# ESQUEMATICO_BOMBA_MESO.net
KiCad netlist of a schematic drawn in Altium Designer
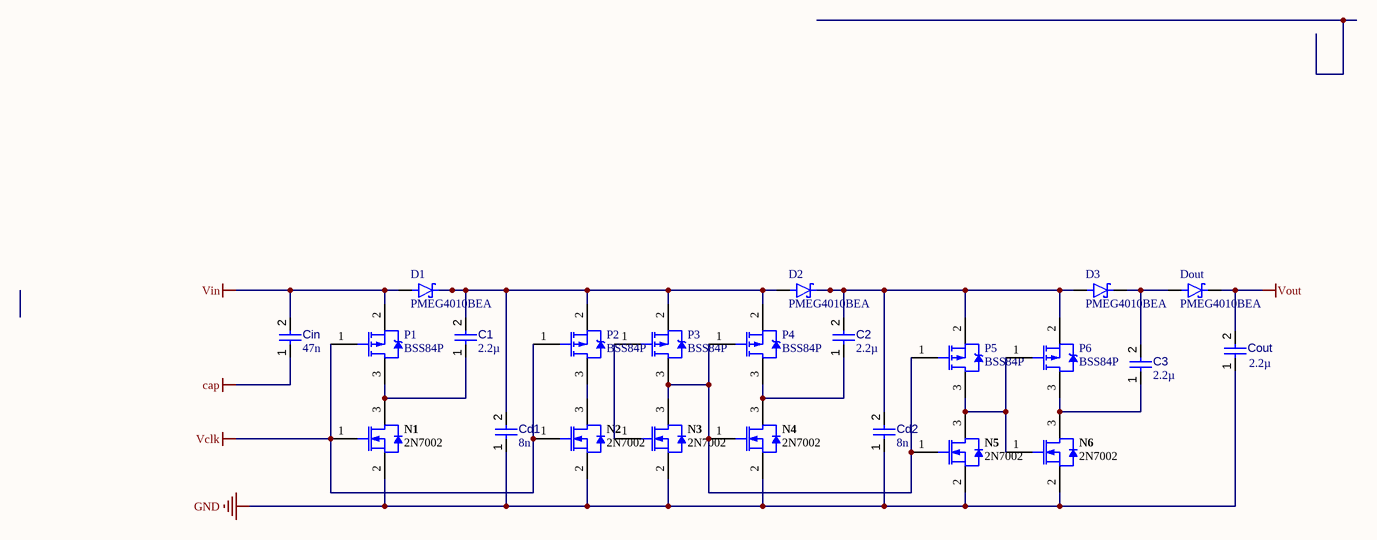
[diagram p0: ESQUEMATICO BOMBA MESO.SchDoc]

(export (version "E")
  (design (tool "Eeschema 10.0.6"))
  (components
    (comp (ref "C1")
      (value "2.2µ")
      (footprint "CAPC2013X135X45NL10T25")
      (description "Chip Capacitor, 10 uF, +/- 10%, 16 V, 0805 (2012 Metric)")
      (fields (field (name "TOLERANCE") "10%") (field (name "Comment") "Capacitor 10 uF +/- 10% 16 V 0805"))
      (libsource (lib "Pontificia Universidad Javeriana") (part "CAP-NP-2"))
    )
    (comp (ref "C2")
      (value "2.2µ")
      (footprint "CAPC2013X135X45NL10T25")
      (description "Chip Capacitor, 10 uF, +/- 10%, 16 V, 0805 (2012 Metric)")
      (fields (field (name "TOLERANCE") "10%") (field (name "Comment") "Capacitor 10 uF +/- 10% 16 V 0805"))
      (libsource (lib "Pontificia Universidad Javeriana") (part "CAP-NP-2"))
    )
    (comp (ref "C3")
      (value "2.2µ")
      (footprint "CAPC2013X135X45NL10T25")
      (description "Chip Capacitor, 10 uF, +/- 10%, 16 V, 0805 (2012 Metric)")
      (fields (field (name "TOLERANCE") "10%") (field (name "Comment") "Capacitor 10 uF +/- 10% 16 V 0805"))
      (libsource (lib "Pontificia Universidad Javeriana") (part "CAP-NP-2"))
    )
    (comp (ref "Cd1")
      (value "8n")
      (footprint "CAPC2013X135X45NL10T25")
      (description "Chip Capacitor, 10 uF, +/- 10%, 16 V, 0805 (2012 Metric)")
      (fields (field (name "TOLERANCE") "10%") (field (name "Comment") "Capacitor 10 uF +/- 10% 16 V 0805"))
      (libsource (lib "Pontificia Universidad Javeriana") (part "CAP-NP-2"))
    )
    (comp (ref "Cd2")
      (value "8n")
      (footprint "CAPC2013X135X45NL10T25")
      (description "Chip Capacitor, 10 uF, +/- 10%, 16 V, 0805 (2012 Metric)")
      (fields (field (name "TOLERANCE") "10%") (field (name "Comment") "Capacitor 10 uF +/- 10% 16 V 0805"))
      (libsource (lib "Pontificia Universidad Javeriana") (part "CAP-NP-2"))
    )
    (comp (ref "Cin")
      (value "47n")
      (footprint "CAPC2013X135X45NL10T25")
      (description "Chip Capacitor, 10 uF, +/- 10%, 16 V, 0805 (2012 Metric)")
      (fields (field (name "TOLERANCE") "10%") (field (name "Comment") "Capacitor 10 uF +/- 10% 16 V 0805"))
      (libsource (lib "Pontificia Universidad Javeriana") (part "CAP-NP-2"))
    )
    (comp (ref "Cout")
      (value "2.2µ")
      (footprint "CAPC2013X135X45NL10T25")
      (description "Chip Capacitor, 10 uF, +/- 10%, 16 V, 0805 (2012 Metric)")
      (fields (field (name "TOLERANCE") "10%") (field (name "Comment") "Capacitor 10 uF +/- 10% 16 V 0805"))
      (libsource (lib "Pontificia Universidad Javeriana") (part "CAP-NP-2"))
    )
    (comp (ref "D1")
      (value "PMEG4010BEA")
      (footprint "DIO_BZX384-C30,115")
      (description "5A, 40V, Schottky Rectifier")
      (fields (field (name "MP") "SS54FSH") (field (name "MF") "Taiwan Semiconductor"))
      (libsource (lib "SS54FSH") (part "SS54FSH"))
    )
    (comp (ref "D2")
      (value "PMEG4010BEA")
      (footprint "DIO_BZX384-C30,115")
      (description "5A, 40V, Schottky Rectifier")
      (fields (field (name "MP") "SS54FSH") (field (name "MF") "Taiwan Semiconductor"))
      (libsource (lib "SS54FSH") (part "SS54FSH"))
    )
    (comp (ref "D3")
      (value "PMEG4010BEA")
      (footprint "DIO_BZX384-C30,115")
      (description "5A, 40V, Schottky Rectifier")
      (fields (field (name "MP") "SS54FSH") (field (name "MF") "Taiwan Semiconductor"))
      (libsource (lib "SS54FSH") (part "SS54FSH"))
    )
    (comp (ref "Dout")
      (value "PMEG4010BEA")
      (footprint "DIO_BZX384-C30,115")
      (description "5A, 40V, Schottky Rectifier")
      (fields (field (name "MP") "SS54FSH") (field (name "MF") "Taiwan Semiconductor"))
      (libsource (lib "SS54FSH") (part "SS54FSH"))
    )
    (comp (ref "N1")
      (value "2N7002")
      (footprint "INF-PG-SOT23_M")
      (fields (field (name "MANUFACTURER") "Infineon"))
      (libsource (lib "Altium Content Vault") (part "INF-NDMOS-GSD-3"))
    )
    (comp (ref "N2")
      (value "2N7002")
      (footprint "INF-PG-SOT23_M")
      (fields (field (name "MANUFACTURER") "Infineon"))
      (libsource (lib "Altium Content Vault") (part "INF-NDMOS-GSD-3"))
    )
    (comp (ref "N3")
      (value "2N7002")
      (footprint "INF-PG-SOT23_M")
      (fields (field (name "MANUFACTURER") "Infineon"))
      (libsource (lib "Altium Content Vault") (part "INF-NDMOS-GSD-3"))
    )
    (comp (ref "N4")
      (value "2N7002")
      (footprint "INF-PG-SOT23_M")
      (fields (field (name "MANUFACTURER") "Infineon"))
      (libsource (lib "Altium Content Vault") (part "INF-NDMOS-GSD-3"))
    )
    (comp (ref "N5")
      (value "2N7002")
      (footprint "INF-PG-SOT23_M")
      (fields (field (name "MANUFACTURER") "Infineon"))
      (libsource (lib "Altium Content Vault") (part "INF-NDMOS-GSD-3"))
    )
    (comp (ref "N6")
      (value "2N7002")
      (footprint "INF-PG-SOT23_M")
      (fields (field (name "MANUFACTURER") "Infineon"))
      (libsource (lib "Altium Content Vault") (part "INF-NDMOS-GSD-3"))
    )
    (comp (ref "P1")
      (value "BSS84P")
      (footprint "INF-PG-SOT23_N")
      (fields (field (name "MANUFACTURER") "Infineon"))
      (libsource (lib "Altium Content Vault") (part "INF-PEMOS-GSD-3-B"))
    )
    (comp (ref "P2")
      (value "BSS84P")
      (footprint "INF-PG-SOT23_N")
      (fields (field (name "MANUFACTURER") "Infineon"))
      (libsource (lib "Altium Content Vault") (part "INF-PEMOS-GSD-3-B"))
    )
    (comp (ref "P3")
      (value "BSS84P")
      (footprint "INF-PG-SOT23_N")
      (fields (field (name "MANUFACTURER") "Infineon"))
      (libsource (lib "Altium Content Vault") (part "INF-PEMOS-GSD-3-B"))
    )
    (comp (ref "P4")
      (value "BSS84P")
      (footprint "INF-PG-SOT23_N")
      (fields (field (name "MANUFACTURER") "Infineon"))
      (libsource (lib "Altium Content Vault") (part "INF-PEMOS-GSD-3-B"))
    )
    (comp (ref "P5")
      (value "BSS84P")
      (footprint "INF-PG-SOT23_N")
      (fields (field (name "MANUFACTURER") "Infineon"))
      (libsource (lib "Altium Content Vault") (part "INF-PEMOS-GSD-3-B"))
    )
    (comp (ref "P6")
      (value "BSS84P")
      (footprint "INF-PG-SOT23_N")
      (fields (field (name "MANUFACTURER") "Infineon"))
      (libsource (lib "Altium Content Vault") (part "INF-PEMOS-GSD-3-B"))
    )
  )
  (nets
    (net (code "1") (name "GND") (class "Default")
      (node (ref "Cd1") (pin "1") (pinfunction "1_1") (pintype "passive"))
      (node (ref "Cd2") (pin "1") (pinfunction "1_1") (pintype "passive"))
      (node (ref "Cout") (pin "1") (pinfunction "1_1") (pintype "passive"))
      (node (ref "N1") (pin "2") (pinfunction "SOURCE_2") (pintype "passive"))
      (node (ref "N2") (pin "2") (pinfunction "SOURCE_2") (pintype "passive"))
      (node (ref "N3") (pin "2") (pinfunction "SOURCE_2") (pintype "passive"))
      (node (ref "N4") (pin "2") (pinfunction "SOURCE_2") (pintype "passive"))
      (node (ref "N5") (pin "2") (pinfunction "SOURCE_2") (pintype "passive"))
      (node (ref "N6") (pin "2") (pinfunction "SOURCE_2") (pintype "passive"))
    )
    (net (code "2") (name "Net-(D1-K)") (class "Default")
      (node (ref "C1") (pin "2") (pinfunction "2_2") (pintype "passive"))
      (node (ref "Cd1") (pin "2") (pinfunction "2_2") (pintype "passive"))
      (node (ref "D1") (pin "C") (pinfunction "K_C") (pintype "passive"))
      (node (ref "D2") (pin "A") (pinfunction "A_A") (pintype "passive"))
      (node (ref "P2") (pin "2") (pinfunction "SOURCE_2") (pintype "passive"))
      (node (ref "P3") (pin "2") (pinfunction "SOURCE_2") (pintype "passive"))
      (node (ref "P4") (pin "2") (pinfunction "SOURCE_2") (pintype "passive"))
    )
    (net (code "3") (name "Net-(D2-K)") (class "Default")
      (node (ref "C2") (pin "2") (pinfunction "2_2") (pintype "passive"))
      (node (ref "Cd2") (pin "2") (pinfunction "2_2") (pintype "passive"))
      (node (ref "D2") (pin "C") (pinfunction "K_C") (pintype "passive"))
      (node (ref "D3") (pin "A") (pinfunction "A_A") (pintype "passive"))
      (node (ref "P5") (pin "2") (pinfunction "SOURCE_2") (pintype "passive"))
      (node (ref "P6") (pin "2") (pinfunction "SOURCE_2") (pintype "passive"))
    )
    (net (code "4") (name "Net-(D3-K)") (class "Default")
      (node (ref "C3") (pin "2") (pinfunction "2_2") (pintype "passive"))
      (node (ref "D3") (pin "C") (pinfunction "K_C") (pintype "passive"))
      (node (ref "Dout") (pin "A") (pinfunction "A_A") (pintype "passive"))
    )
    (net (code "5") (name "Net-(N1-DRAIN)") (class "Default")
      (node (ref "C1") (pin "1") (pinfunction "1_1") (pintype "passive"))
      (node (ref "N1") (pin "3") (pinfunction "DRAIN_3") (pintype "passive"))
      (node (ref "P1") (pin "3") (pinfunction "DRAIN_3") (pintype "passive"))
    )
    (net (code "6") (name "Net-(N2-DRAIN)") (class "Default")
      (node (ref "N2") (pin "3") (pinfunction "DRAIN_3") (pintype "passive"))
      (node (ref "P2") (pin "3") (pinfunction "DRAIN_3") (pintype "passive"))
    )
    (net (code "7") (name "Net-(N3-DRAIN)") (class "Default")
      (node (ref "N3") (pin "3") (pinfunction "DRAIN_3") (pintype "passive"))
      (node (ref "N4") (pin "1") (pinfunction "GATE_1") (pintype "passive"))
      (node (ref "N5") (pin "1") (pinfunction "GATE_1") (pintype "passive"))
      (node (ref "P3") (pin "3") (pinfunction "DRAIN_3") (pintype "passive"))
      (node (ref "P4") (pin "1") (pinfunction "GATE_1") (pintype "passive"))
      (node (ref "P5") (pin "1") (pinfunction "GATE_1") (pintype "passive"))
    )
    (net (code "8") (name "Net-(N3-GATE)") (class "Default")
      (node (ref "N3") (pin "1") (pinfunction "GATE_1") (pintype "passive"))
      (node (ref "P3") (pin "1") (pinfunction "GATE_1") (pintype "passive"))
    )
    (net (code "9") (name "Net-(N4-DRAIN)") (class "Default")
      (node (ref "C2") (pin "1") (pinfunction "1_1") (pintype "passive"))
      (node (ref "N4") (pin "3") (pinfunction "DRAIN_3") (pintype "passive"))
      (node (ref "P4") (pin "3") (pinfunction "DRAIN_3") (pintype "passive"))
    )
    (net (code "10") (name "Net-(N5-DRAIN)") (class "Default")
      (node (ref "N5") (pin "3") (pinfunction "DRAIN_3") (pintype "passive"))
      (node (ref "N6") (pin "1") (pinfunction "GATE_1") (pintype "passive"))
      (node (ref "P5") (pin "3") (pinfunction "DRAIN_3") (pintype "passive"))
      (node (ref "P6") (pin "1") (pinfunction "GATE_1") (pintype "passive"))
    )
    (net (code "11") (name "Net-(N6-DRAIN)") (class "Default")
      (node (ref "C3") (pin "1") (pinfunction "1_1") (pintype "passive"))
      (node (ref "N6") (pin "3") (pinfunction "DRAIN_3") (pintype "passive"))
      (node (ref "P6") (pin "3") (pinfunction "DRAIN_3") (pintype "passive"))
    )
    (net (code "12") (name "Vclk") (class "Default")
      (node (ref "N1") (pin "1") (pinfunction "GATE_1") (pintype "passive"))
      (node (ref "N2") (pin "1") (pinfunction "GATE_1") (pintype "passive"))
      (node (ref "P1") (pin "1") (pinfunction "GATE_1") (pintype "passive"))
      (node (ref "P2") (pin "1") (pinfunction "GATE_1") (pintype "passive"))
    )
    (net (code "13") (name "Vin") (class "Default")
      (node (ref "Cin") (pin "2") (pinfunction "2_2") (pintype "passive"))
      (node (ref "D1") (pin "A") (pinfunction "A_A") (pintype "passive"))
      (node (ref "P1") (pin "2") (pinfunction "SOURCE_2") (pintype "passive"))
    )
    (net (code "14") (name "Vout") (class "Default")
      (node (ref "Cout") (pin "2") (pinfunction "2_2") (pintype "passive"))
      (node (ref "Dout") (pin "C") (pinfunction "K_C") (pintype "passive"))
    )
    (net (code "15") (name "cap") (class "Default")
      (node (ref "Cin") (pin "1") (pinfunction "1_1") (pintype "passive"))
    )
  )
)
